# SCH_ExpansionModule.net
KiCad netlist of a schematic drawn in EasyEDA
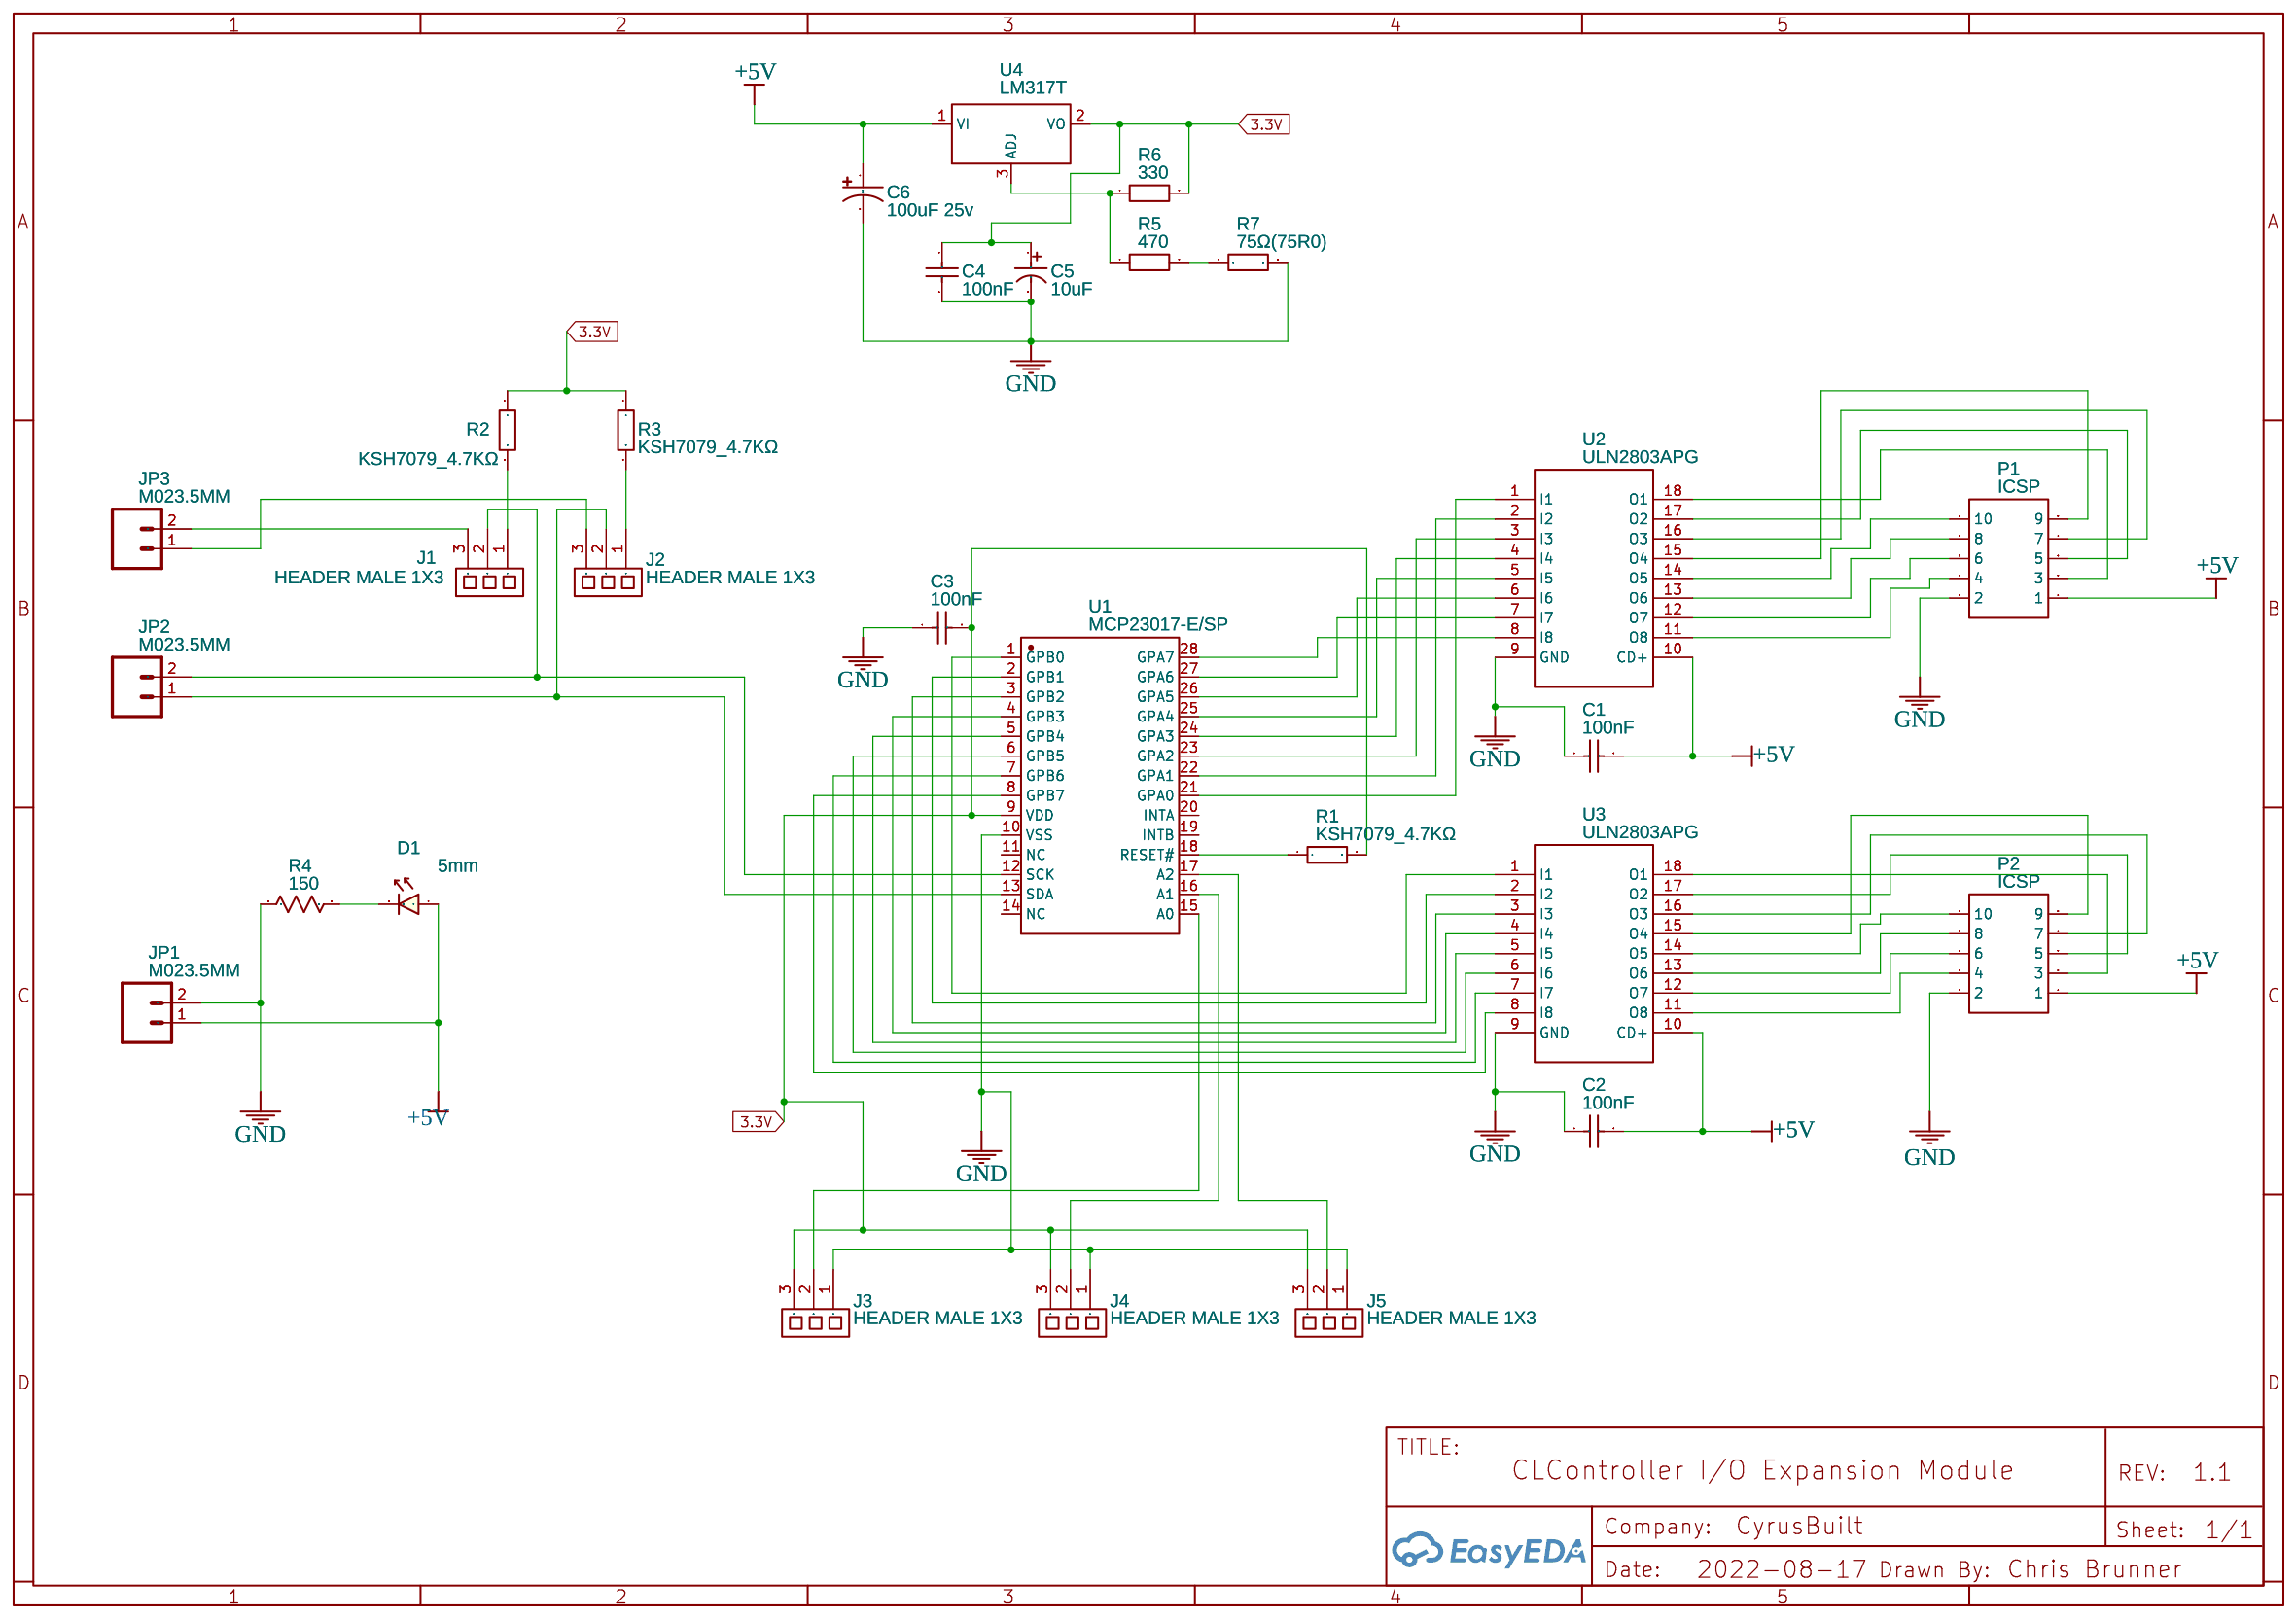
[diagram p0: schematic sheet]

(export (version "E")
  (design (tool "Eeschema 10.0.6"))
  (components
    (comp (ref "C1")
      (value "100nF")
      (fields
        (field (name "BOM_Manufacturer Part") "CT4-0805Y104M500")
        (field (name "BOM_Supplier Part") "C46756")
      )
      (libsource (lib "") (part "100nF"))
    )
    (comp (ref "C2")
      (value "100nF")
      (fields
        (field (name "BOM_Manufacturer Part") "CT4-0805Y104M500")
        (field (name "BOM_Supplier Part") "C46756")
      )
      (libsource (lib "") (part "100nF"))
    )
    (comp (ref "C3")
      (value "100nF")
      (fields
        (field (name "BOM_Manufacturer Part") "CT4-0805Y104M500")
        (field (name "BOM_Supplier Part") "C46756")
      )
      (libsource (lib "") (part "100nF"))
    )
    (comp (ref "C4")
      (value "100nF")
      (fields
        (field (name "BOM_Manufacturer Part") "CT4-0805Y104M500")
        (field (name "BOM_Supplier Part") "C46756")
      )
      (libsource (lib "") (part "100nF_1"))
    )
    (comp (ref "C5")
      (value "10uF")
      (fields
        (field (name "BOM_Manufacturer Part") "10uF 50V白纸 13*25")
        (field (name "BOM_Supplier Part") "C43814")
      )
      (libsource (lib "") (part "10uF 50V ChongX"))
    )
    (comp (ref "C6") (value "100uF 25v") (libsource (lib "") (part "100UF/25V")))
    (comp (ref "D1")
      (value "5mm")
      (fields (field (name "BOM_Manufacturer Part") "L-1503EC") (field (name "BOM_Supplier Part") "1003201"))
      (libsource (lib "") (part "RED LED"))
    )
    (comp (ref "J1") (value "HEADER MALE 1X3") (libsource (lib "") (part "HEADER MALE 1X3")))
    (comp (ref "J2") (value "HEADER MALE 1X3") (libsource (lib "") (part "HEADER MALE 1X3")))
    (comp (ref "J3") (value "HEADER MALE 1X3") (libsource (lib "") (part "HEADER MALE 1X3")))
    (comp (ref "J4") (value "HEADER MALE 1X3") (libsource (lib "") (part "HEADER MALE 1X3")))
    (comp (ref "J5") (value "HEADER MALE 1X3") (libsource (lib "") (part "HEADER MALE 1X3")))
    (comp (ref "JP1") (value "M023.5MM") (libsource (lib "") (part "M023.5MM")))
    (comp (ref "JP2") (value "M023.5MM") (libsource (lib "") (part "M023.5MM")))
    (comp (ref "JP3") (value "M023.5MM") (libsource (lib "") (part "M023.5MM")))
    (comp (ref "P1")
      (value "ICSP")
      (fields
        (field (name "BOM_Manufacturer Part") "IDC Box 2.54mm 2X5P")
        (field (name "BOM_Supplier Part") "C5665")
      )
      (libsource (lib "") (part "ICSP"))
    )
    (comp (ref "P2")
      (value "ICSP")
      (fields
        (field (name "BOM_Manufacturer Part") "IDC Box 2.54mm 2X5P")
        (field (name "BOM_Supplier Part") "C5665")
      )
      (libsource (lib "") (part "ICSP"))
    )
    (comp (ref "R1")
      (value "KSH7079_4.7KΩ")
      (fields
        (field (name "BOM_Manufacturer Part") "MFR0W4F2200A50")
        (field (name "BOM_Supplier Part") "E57439")
      )
      (libsource (lib "") (part "KSH7079_4.7KΩ"))
    )
    (comp (ref "R2")
      (value "KSH7079_4.7KΩ")
      (fields
        (field (name "BOM_Manufacturer Part") "MFR0W4F2200A50")
        (field (name "BOM_Supplier Part") "E57439")
      )
      (libsource (lib "") (part "KSH7079_4.7KΩ_1"))
    )
    (comp (ref "R3")
      (value "KSH7079_4.7KΩ")
      (fields
        (field (name "BOM_Manufacturer Part") "MFR0W4F2200A50")
        (field (name "BOM_Supplier Part") "E57439")
      )
      (libsource (lib "") (part "KSH7079_4.7KΩ_1"))
    )
    (comp (ref "R4")
      (value "150")
      (fields
        (field (name "BOM_Manufacturer Part") "MCF 0.25W 150R")
        (field (name "BOM_Supplier Part") "9339175")
      )
      (libsource (lib "") (part "MCF 0.25W 150R"))
    )
    (comp (ref "R5") (value "470") (libsource (lib "") (part "470")))
    (comp (ref "R6") (value "330") (libsource (lib "") (part "330")))
    (comp (ref "R7")
      (value "75Ω(75R0)")
      (fields
        (field (name "BOM_Manufacturer Part") "MF1/8W-75Ω±1% T52")
        (field (name "BOM_Supplier Part") "C119155")
      )
      (libsource (lib "") (part "MF1/8W-75Ω±1% T52"))
    )
    (comp (ref "U1")
      (value "MCP23017-E/SP")
      (fields (field (name "BOM_Supplier Part") "C647352"))
      (libsource (lib "") (part "MCP23017-E/SP"))
    )
    (comp (ref "U2")
      (value "ULN2803APG")
      (fields (field (name "BOM_Supplier Part") "C5252"))
      (libsource (lib "") (part "ULN2803APG"))
    )
    (comp (ref "U3")
      (value "ULN2803APG")
      (fields (field (name "BOM_Supplier Part") "C5252"))
      (libsource (lib "") (part "ULN2803APG"))
    )
    (comp (ref "U4")
      (value "LM317T")
      (fields (field (name "BOM_Supplier Part") "511-LM317T"))
      (libsource (lib "") (part "LM317T"))
    )
  )
  (nets
    (net (code "1") (name "+5V") (class "Default")
      (node (ref "C1") (pin "2") (pinfunction "2_2") (pintype "input"))
      (node (ref "C2") (pin "2") (pinfunction "2_2") (pintype "input"))
      (node (ref "C6") (pin "1") (pinfunction "1_1") (pintype "unspecified"))
      (node (ref "D1") (pin "1") (pinfunction "1_1") (pintype "unspecified"))
      (node (ref "JP1") (pin "1") (pinfunction "1_1") (pintype "bidirectional"))
      (node (ref "P1") (pin "1") (pinfunction "1_1") (pintype "unspecified"))
      (node (ref "P2") (pin "1") (pinfunction "1_1") (pintype "unspecified"))
      (node (ref "U2") (pin "10") (pinfunction "CD+_10") (pintype "unspecified"))
      (node (ref "U3") (pin "10") (pinfunction "CD+_10") (pintype "unspecified"))
      (node (ref "U4") (pin "1") (pinfunction "VI_1") (pintype "input"))
    )
    (net (code "2") (name "3.3V") (class "Default")
      (node (ref "C3") (pin "2") (pinfunction "2_2") (pintype "input"))
      (node (ref "C4") (pin "1") (pinfunction "1_1") (pintype "input"))
      (node (ref "C5") (pin "1") (pinfunction "1_1") (pintype "input"))
      (node (ref "J3") (pin "3") (pinfunction "3_3") (pintype "unspecified"))
      (node (ref "J4") (pin "3") (pinfunction "3_3") (pintype "unspecified"))
      (node (ref "J5") (pin "3") (pinfunction "3_3") (pintype "unspecified"))
      (node (ref "R1") (pin "2") (pinfunction "2_2") (pintype "input"))
      (node (ref "R2") (pin "1") (pinfunction "1_1") (pintype "input"))
      (node (ref "R3") (pin "1") (pinfunction "1_1") (pintype "input"))
      (node (ref "R6") (pin "2") (pintype "unspecified"))
      (node (ref "U1") (pin "9") (pinfunction "VDD_9") (pintype "unspecified"))
      (node (ref "U4") (pin "2") (pinfunction "VO_2") (pintype "unspecified"))
    )
    (net (code "3") (name "GND") (class "Default")
      (node (ref "C1") (pin "1") (pinfunction "1_1") (pintype "input"))
      (node (ref "C2") (pin "1") (pinfunction "1_1") (pintype "input"))
      (node (ref "C3") (pin "1") (pinfunction "1_1") (pintype "input"))
      (node (ref "C4") (pin "2") (pinfunction "2_2") (pintype "input"))
      (node (ref "C5") (pin "2") (pinfunction "2_2") (pintype "input"))
      (node (ref "C6") (pin "2") (pinfunction "2_2") (pintype "unspecified"))
      (node (ref "J3") (pin "1") (pinfunction "1_1") (pintype "unspecified"))
      (node (ref "J4") (pin "1") (pinfunction "1_1") (pintype "unspecified"))
      (node (ref "J5") (pin "1") (pinfunction "1_1") (pintype "unspecified"))
      (node (ref "JP1") (pin "2") (pinfunction "2_2") (pintype "bidirectional"))
      (node (ref "P1") (pin "2") (pinfunction "2_2") (pintype "unspecified"))
      (node (ref "P2") (pin "2") (pinfunction "2_2") (pintype "unspecified"))
      (node (ref "R4") (pin "1") (pinfunction "1_1") (pintype "unspecified"))
      (node (ref "R7") (pin "2") (pinfunction "2_2") (pintype "input"))
      (node (ref "U1") (pin "10") (pinfunction "VSS_10") (pintype "unspecified"))
      (node (ref "U2") (pin "9") (pinfunction "GND_9") (pintype "passive"))
      (node (ref "U3") (pin "9") (pinfunction "GND_9") (pintype "passive"))
    )
    (net (code "4") (name "Net-(D1-Pad2)") (class "Default")
      (node (ref "D1") (pin "2") (pinfunction "2_2") (pintype "unspecified"))
      (node (ref "R4") (pin "2") (pinfunction "2_2") (pintype "unspecified"))
    )
    (net (code "5") (name "Net-(J1-Pad1)") (class "Default")
      (node (ref "J1") (pin "1") (pinfunction "1_1") (pintype "unspecified"))
      (node (ref "R2") (pin "2") (pinfunction "2_2") (pintype "input"))
    )
    (net (code "6") (name "Net-(J1-Pad3)") (class "Default")
      (node (ref "J1") (pin "3") (pinfunction "3_3") (pintype "unspecified"))
      (node (ref "JP3") (pin "2") (pinfunction "2_2") (pintype "bidirectional"))
    )
    (net (code "7") (name "Net-(J2-Pad1)") (class "Default")
      (node (ref "J2") (pin "1") (pinfunction "1_1") (pintype "unspecified"))
      (node (ref "R3") (pin "2") (pinfunction "2_2") (pintype "input"))
    )
    (net (code "8") (name "Net-(J2-Pad3)") (class "Default")
      (node (ref "J2") (pin "3") (pinfunction "3_3") (pintype "unspecified"))
      (node (ref "JP3") (pin "1") (pinfunction "1_1") (pintype "bidirectional"))
    )
    (net (code "9") (name "Net-(R5-Pad2)") (class "Default")
      (node (ref "R5") (pin "2") (pintype "unspecified"))
      (node (ref "R7") (pin "1") (pinfunction "1_1") (pintype "input"))
    )
    (net (code "10") (name "Net-(U1-A0)") (class "Default")
      (node (ref "J3") (pin "2") (pinfunction "2_2") (pintype "unspecified"))
      (node (ref "U1") (pin "15") (pinfunction "A0_15") (pintype "unspecified"))
    )
    (net (code "11") (name "Net-(U1-A1)") (class "Default")
      (node (ref "J4") (pin "2") (pinfunction "2_2") (pintype "unspecified"))
      (node (ref "U1") (pin "16") (pinfunction "A1_16") (pintype "unspecified"))
    )
    (net (code "12") (name "Net-(U1-A2)") (class "Default")
      (node (ref "J5") (pin "2") (pinfunction "2_2") (pintype "unspecified"))
      (node (ref "U1") (pin "17") (pinfunction "A2_17") (pintype "unspecified"))
    )
    (net (code "13") (name "Net-(U1-GPA0)") (class "Default")
      (node (ref "U1") (pin "21") (pinfunction "GPA0_21") (pintype "unspecified"))
      (node (ref "U2") (pin "1") (pinfunction "I1_1") (pintype "input"))
    )
    (net (code "14") (name "Net-(U1-GPA1)") (class "Default")
      (node (ref "U1") (pin "22") (pinfunction "GPA1_22") (pintype "unspecified"))
      (node (ref "U2") (pin "2") (pinfunction "I2_2") (pintype "input"))
    )
    (net (code "15") (name "Net-(U1-GPA2)") (class "Default")
      (node (ref "U1") (pin "23") (pinfunction "GPA2_23") (pintype "unspecified"))
      (node (ref "U2") (pin "3") (pinfunction "I3_3") (pintype "input"))
    )
    (net (code "16") (name "Net-(U1-GPA3)") (class "Default")
      (node (ref "U1") (pin "24") (pinfunction "GPA3_24") (pintype "unspecified"))
      (node (ref "U2") (pin "4") (pinfunction "I4_4") (pintype "input"))
    )
    (net (code "17") (name "Net-(U1-GPA4)") (class "Default")
      (node (ref "U1") (pin "25") (pinfunction "GPA4_25") (pintype "unspecified"))
      (node (ref "U2") (pin "5") (pinfunction "I5_5") (pintype "input"))
    )
    (net (code "18") (name "Net-(U1-GPA5)") (class "Default")
      (node (ref "U1") (pin "26") (pinfunction "GPA5_26") (pintype "unspecified"))
      (node (ref "U2") (pin "6") (pinfunction "I6_6") (pintype "input"))
    )
    (net (code "19") (name "Net-(U1-GPA6)") (class "Default")
      (node (ref "U1") (pin "27") (pinfunction "GPA6_27") (pintype "unspecified"))
      (node (ref "U2") (pin "7") (pinfunction "I7_7") (pintype "input"))
    )
    (net (code "20") (name "Net-(U1-GPA7)") (class "Default")
      (node (ref "U1") (pin "28") (pinfunction "GPA7_28") (pintype "unspecified"))
      (node (ref "U2") (pin "8") (pinfunction "I8_8") (pintype "input"))
    )
    (net (code "21") (name "Net-(U1-GPB0)") (class "Default")
      (node (ref "U1") (pin "1") (pinfunction "GPB0_1") (pintype "unspecified"))
      (node (ref "U3") (pin "1") (pinfunction "I1_1") (pintype "input"))
    )
    (net (code "22") (name "Net-(U1-GPB1)") (class "Default")
      (node (ref "U1") (pin "2") (pinfunction "GPB1_2") (pintype "unspecified"))
      (node (ref "U3") (pin "2") (pinfunction "I2_2") (pintype "input"))
    )
    (net (code "23") (name "Net-(U1-GPB2)") (class "Default")
      (node (ref "U1") (pin "3") (pinfunction "GPB2_3") (pintype "unspecified"))
      (node (ref "U3") (pin "3") (pinfunction "I3_3") (pintype "input"))
    )
    (net (code "24") (name "Net-(U1-GPB3)") (class "Default")
      (node (ref "U1") (pin "4") (pinfunction "GPB3_4") (pintype "unspecified"))
      (node (ref "U3") (pin "4") (pinfunction "I4_4") (pintype "input"))
    )
    (net (code "25") (name "Net-(U1-GPB4)") (class "Default")
      (node (ref "U1") (pin "5") (pinfunction "GPB4_5") (pintype "unspecified"))
      (node (ref "U3") (pin "5") (pinfunction "I5_5") (pintype "input"))
    )
    (net (code "26") (name "Net-(U1-GPB5)") (class "Default")
      (node (ref "U1") (pin "6") (pinfunction "GPB5_6") (pintype "unspecified"))
      (node (ref "U3") (pin "6") (pinfunction "I6_6") (pintype "input"))
    )
    (net (code "27") (name "Net-(U1-GPB6)") (class "Default")
      (node (ref "U1") (pin "7") (pinfunction "GPB6_7") (pintype "unspecified"))
      (node (ref "U3") (pin "7") (pinfunction "I7_7") (pintype "input"))
    )
    (net (code "28") (name "Net-(U1-GPB7)") (class "Default")
      (node (ref "U1") (pin "8") (pinfunction "GPB7_8") (pintype "unspecified"))
      (node (ref "U3") (pin "8") (pinfunction "I8_8") (pintype "input"))
    )
    (net (code "29") (name "Net-(U1-RESET#)") (class "Default")
      (node (ref "R1") (pin "1") (pinfunction "1_1") (pintype "input"))
      (node (ref "U1") (pin "18") (pinfunction "RESET#_18") (pintype "unspecified"))
    )
    (net (code "30") (name "Net-(U1-SCK)") (class "Default")
      (node (ref "J1") (pin "2") (pinfunction "2_2") (pintype "unspecified"))
      (node (ref "JP2") (pin "2") (pinfunction "2_2") (pintype "bidirectional"))
      (node (ref "U1") (pin "12") (pinfunction "SCK_12") (pintype "unspecified"))
    )
    (net (code "31") (name "Net-(U1-SDA)") (class "Default")
      (node (ref "J2") (pin "2") (pinfunction "2_2") (pintype "unspecified"))
      (node (ref "JP2") (pin "1") (pinfunction "1_1") (pintype "bidirectional"))
      (node (ref "U1") (pin "13") (pinfunction "SDA_13") (pintype "unspecified"))
    )
    (net (code "32") (name "Net-(U2-O1)") (class "Default")
      (node (ref "P1") (pin "3") (pinfunction "3_3") (pintype "unspecified"))
      (node (ref "U2") (pin "18") (pinfunction "O1_18") (pintype "unspecified"))
    )
    (net (code "33") (name "Net-(U2-O2)") (class "Default")
      (node (ref "P1") (pin "5") (pinfunction "5_5") (pintype "unspecified"))
      (node (ref "U2") (pin "17") (pinfunction "O2_17") (pintype "unspecified"))
    )
    (net (code "34") (name "Net-(U2-O3)") (class "Default")
      (node (ref "P1") (pin "7") (pinfunction "7_7") (pintype "unspecified"))
      (node (ref "U2") (pin "16") (pinfunction "O3_16") (pintype "unspecified"))
    )
    (net (code "35") (name "Net-(U2-O4)") (class "Default")
      (node (ref "P1") (pin "9") (pinfunction "9_9") (pintype "unspecified"))
      (node (ref "U2") (pin "15") (pinfunction "O4_15") (pintype "unspecified"))
    )
    (net (code "36") (name "Net-(U2-O5)") (class "Default")
      (node (ref "P1") (pin "10") (pinfunction "10_10") (pintype "unspecified"))
      (node (ref "U2") (pin "14") (pinfunction "O5_14") (pintype "unspecified"))
    )
    (net (code "37") (name "Net-(U2-O6)") (class "Default")
      (node (ref "P1") (pin "8") (pinfunction "8_8") (pintype "unspecified"))
      (node (ref "U2") (pin "13") (pinfunction "O6_13") (pintype "unspecified"))
    )
    (net (code "38") (name "Net-(U2-O7)") (class "Default")
      (node (ref "P1") (pin "6") (pinfunction "6_6") (pintype "unspecified"))
      (node (ref "U2") (pin "12") (pinfunction "O7_12") (pintype "unspecified"))
    )
    (net (code "39") (name "Net-(U2-O8)") (class "Default")
      (node (ref "P1") (pin "4") (pinfunction "4_4") (pintype "unspecified"))
      (node (ref "U2") (pin "11") (pinfunction "O8_11") (pintype "unspecified"))
    )
    (net (code "40") (name "Net-(U3-O1)") (class "Default")
      (node (ref "P2") (pin "3") (pinfunction "3_3") (pintype "unspecified"))
      (node (ref "U3") (pin "18") (pinfunction "O1_18") (pintype "unspecified"))
    )
    (net (code "41") (name "Net-(U3-O2)") (class "Default")
      (node (ref "P2") (pin "5") (pinfunction "5_5") (pintype "unspecified"))
      (node (ref "U3") (pin "17") (pinfunction "O2_17") (pintype "unspecified"))
    )
    (net (code "42") (name "Net-(U3-O3)") (class "Default")
      (node (ref "P2") (pin "7") (pinfunction "7_7") (pintype "unspecified"))
      (node (ref "U3") (pin "16") (pinfunction "O3_16") (pintype "unspecified"))
    )
    (net (code "43") (name "Net-(U3-O4)") (class "Default")
      (node (ref "P2") (pin "9") (pinfunction "9_9") (pintype "unspecified"))
      (node (ref "U3") (pin "15") (pinfunction "O4_15") (pintype "unspecified"))
    )
    (net (code "44") (name "Net-(U3-O5)") (class "Default")
      (node (ref "P2") (pin "10") (pinfunction "10_10") (pintype "unspecified"))
      (node (ref "U3") (pin "14") (pinfunction "O5_14") (pintype "unspecified"))
    )
    (net (code "45") (name "Net-(U3-O6)") (class "Default")
      (node (ref "P2") (pin "8") (pinfunction "8_8") (pintype "unspecified"))
      (node (ref "U3") (pin "13") (pinfunction "O6_13") (pintype "unspecified"))
    )
    (net (code "46") (name "Net-(U3-O7)") (class "Default")
      (node (ref "P2") (pin "6") (pinfunction "6_6") (pintype "unspecified"))
      (node (ref "U3") (pin "12") (pinfunction "O7_12") (pintype "unspecified"))
    )
    (net (code "47") (name "Net-(U3-O8)") (class "Default")
      (node (ref "P2") (pin "4") (pinfunction "4_4") (pintype "unspecified"))
      (node (ref "U3") (pin "11") (pinfunction "O8_11") (pintype "unspecified"))
    )
    (net (code "48") (name "Net-(U4-ADJ)") (class "Default")
      (node (ref "R5") (pin "1") (pintype "unspecified"))
      (node (ref "R6") (pin "1") (pintype "unspecified"))
      (node (ref "U4") (pin "3") (pinfunction "ADJ_3") (pintype "unspecified"))
    )
    (net (code "49") (name "unconnected-(U1-INTA-Pad20)") (class "Default")
      (node (ref "U1") (pin "20") (pinfunction "INTA_20") (pintype "unspecified"))
    )
    (net (code "50") (name "unconnected-(U1-INTB-Pad19)") (class "Default")
      (node (ref "U1") (pin "19") (pinfunction "INTB_19") (pintype "unspecified"))
    )
    (net (code "51") (name "unconnected-(U1-NC-Pad11)") (class "Default")
      (node (ref "U1") (pin "11") (pinfunction "NC_11") (pintype "unspecified"))
    )
    (net (code "52") (name "unconnected-(U1-NC-Pad14)") (class "Default")
      (node (ref "U1") (pin "14") (pinfunction "NC_14") (pintype "unspecified"))
    )
  )
)
